# Main.net
KiCad netlist of a schematic drawn in Altium Designer
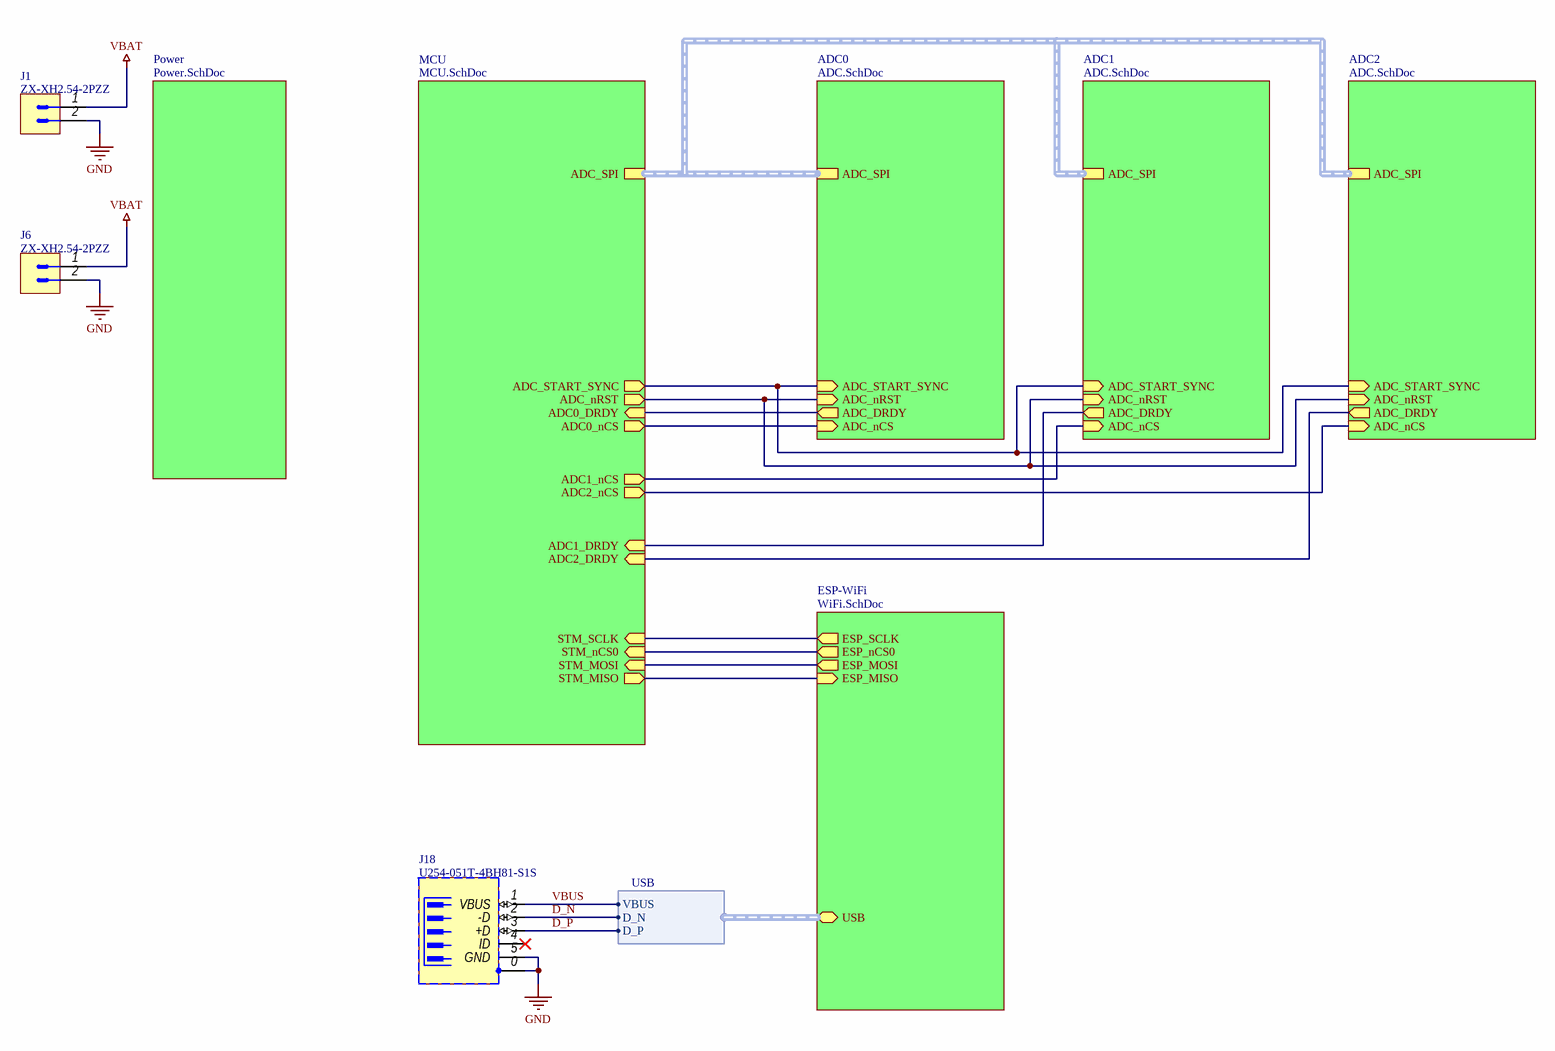
[diagram p0: Main.SchDoc]

(export (version "E")
  (design (tool "Eeschema 10.0.6"))
  (components
    (comp (ref "J1")
      (value "ZX-XH2.54-2PZZ")
      (footprint "XH2.54-2PZZ")
      (fields (field (name "AUTHOR") "Krepak V."))
      (libsource (lib "tgl_lib_altium") (part "Connector 2 Male"))
    )
    (comp (ref "J6")
      (value "ZX-XH2.54-2PZZ")
      (footprint "XH2.54-2PZZ")
      (fields (field (name "AUTHOR") "Krepak V."))
      (libsource (lib "tgl_lib_altium") (part "Connector 2 Male"))
    )
    (comp (ref "J18")
      (value "U254-051T-4BH81-S1S")
      (footprint "U254-051T-4BH81-S1S")
      (fields (field (name "AUTHOR") "Krepak V."))
      (libsource (lib "tgl_lib_altium") (part "Connector USB 5 Pin + 1Shield"))
    )
  )
  (nets
    (net (code "11") (name "/D_N") (class "Default")
      (node (ref "J18") (pin "2") (pinfunction "-D_2") (pintype "bidirectional"))
    )
    (net (code "12") (name "/D_P") (class "Default")
      (node (ref "J18") (pin "3") (pinfunction "+D_3") (pintype "bidirectional"))
    )
    (net (code "17") (name "/VBUS") (class "Default")
      (node (ref "J18") (pin "1") (pinfunction "VBUS_1") (pintype "bidirectional"))
    )
    (net (code "19") (name "GND") (class "Default")
      (node (ref "J1") (pin "2") (pinfunction "2_2") (pintype "power_in"))
      (node (ref "J18") (pin "0") (pinfunction "SH_0") (pintype "power_in"))
      (node (ref "J18") (pin "5") (pinfunction "GND_5") (pintype "power_in"))
      (node (ref "J6") (pin "2") (pinfunction "2_2") (pintype "power_in"))
    )
    (net (code "20") (name "VBAT") (class "Default")
      (node (ref "J1") (pin "1") (pinfunction "1_1") (pintype "power_in"))
      (node (ref "J6") (pin "1") (pinfunction "1_1") (pintype "power_in"))
    )
    (net (code "21") (name "unconnected-(J18-ID-Pad4)") (class "Default")
      (node (ref "J18") (pin "4") (pinfunction "ID_4") (pintype "passive+no_connect"))
    )
  )
)
